# Proyek6_Joy.net
KiCad netlist of a schematic drawn in EasyEDA
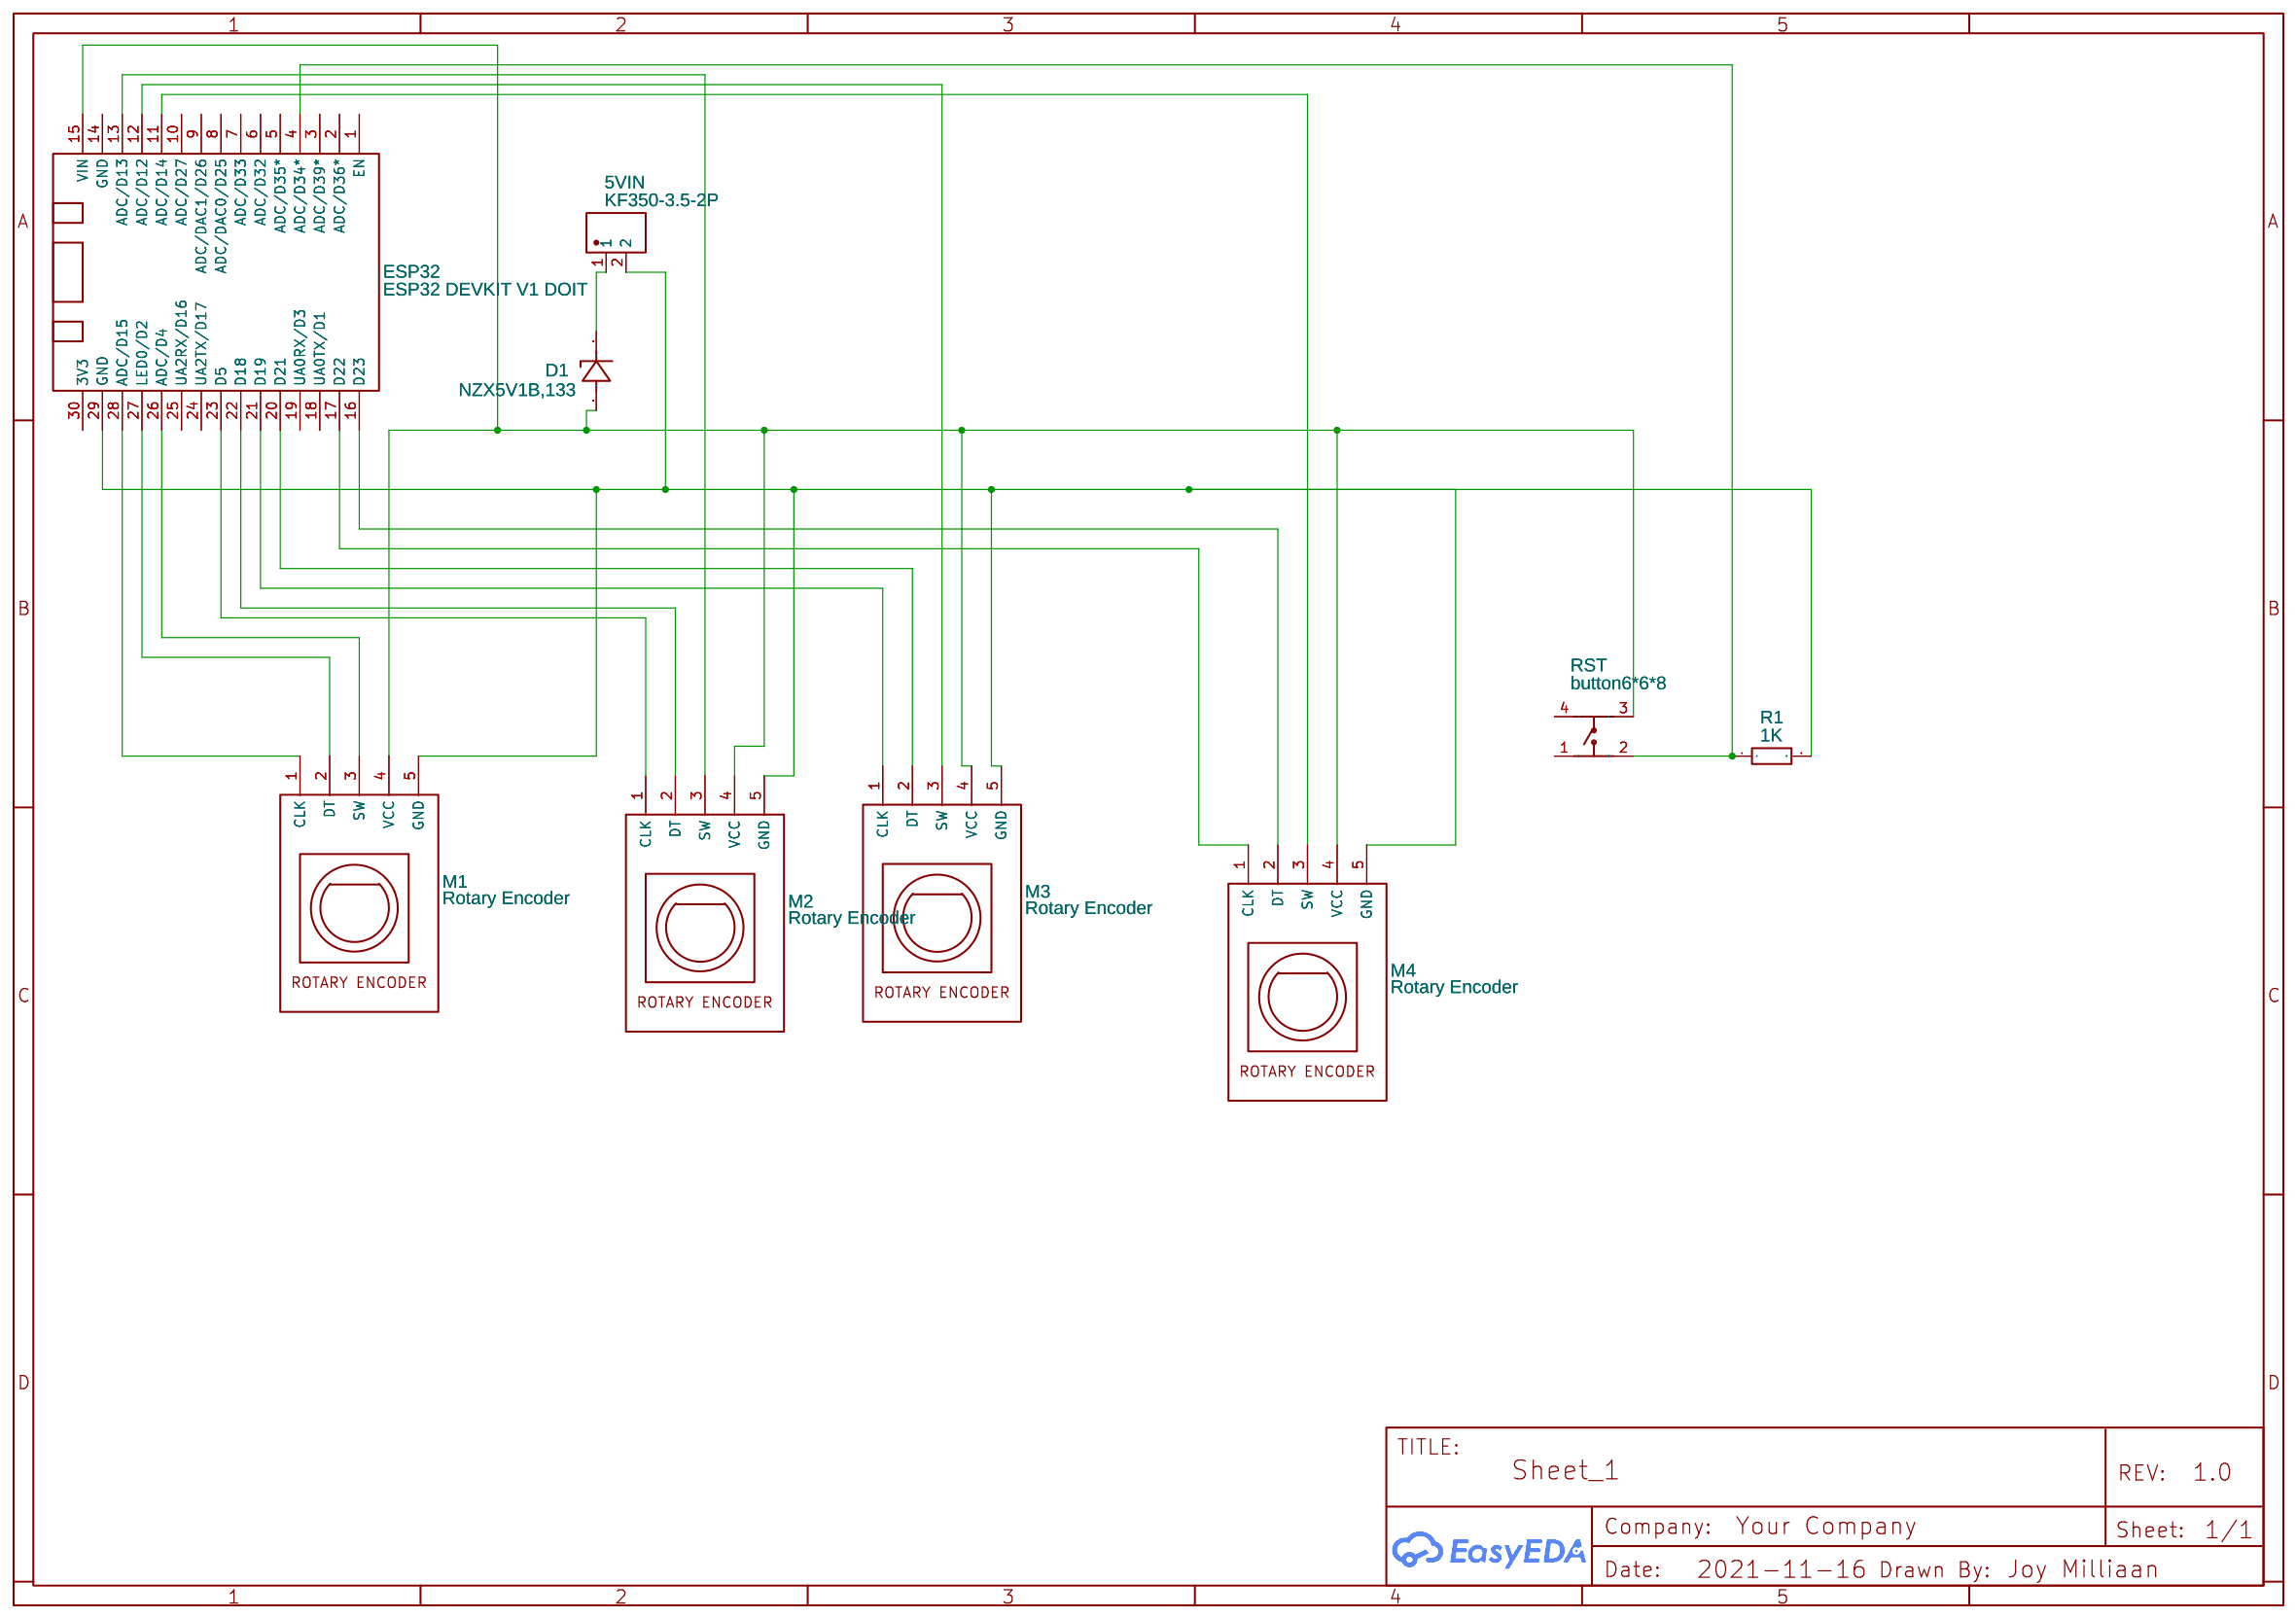
[diagram p0: schematic sheet]

(export (version "E")
  (design (tool "Eeschema 10.0.6"))
  (components
    (comp (ref "5VIN")
      (value "KF350-3.5-2P")
      (fields (field (name "BOM_Supplier Part") "C474892"))
      (libsource (lib "") (part "KF350-3.5-2P"))
    )
    (comp (ref "D1")
      (value "NZX5V1B,133")
      (fields (field (name "BOM_Supplier Part") "C551729"))
      (libsource (lib "") (part "NZX5V1B,133"))
    )
    (comp (ref "ESP32") (value "ESP32 DEVKIT V1 DOIT") (libsource (lib "") (part "ESP32 DEVKIT V1 DOIT")))
    (comp (ref "M1")
      (value "Rotary Encoder")
      (fields (field (name "BOM_Manufacturer Part") "KY-040"))
      (libsource (lib "") (part "Rotary Encoder"))
    )
    (comp (ref "M2")
      (value "Rotary Encoder")
      (fields (field (name "BOM_Manufacturer Part") "KY-040"))
      (libsource (lib "") (part "Rotary Encoder"))
    )
    (comp (ref "M3")
      (value "Rotary Encoder")
      (fields (field (name "BOM_Manufacturer Part") "KY-040"))
      (libsource (lib "") (part "Rotary Encoder"))
    )
    (comp (ref "M4")
      (value "Rotary Encoder")
      (fields (field (name "BOM_Manufacturer Part") "KY-040"))
      (libsource (lib "") (part "Rotary Encoder"))
    )
    (comp (ref "R1")
      (value "1K")
      (fields
        (field (name "BOM_Manufacturer Part") "CFR0W4J0102A50")
        (field (name "BOM_Supplier Part") "C61293")
      )
      (libsource (lib "") (part "CFR0W4J0102A50"))
    )
    (comp (ref "RST")
      (value "button6*6*8")
      (fields (field (name "BOM_Supplier Part") "C59982"))
      (libsource (lib "") (part "button6*6*8"))
    )
  )
  (nets
    (net (code "1") (name "Net-(D1-A)") (class "Default")
      (node (ref "D1") (pin "2") (pinfunction "A_2") (pintype "unspecified"))
      (node (ref "ESP32") (pin "15") (pinfunction "VIN_15") (pintype "input"))
      (node (ref "M1") (pin "4") (pinfunction "VCC_4") (pintype "unspecified"))
      (node (ref "M2") (pin "4") (pinfunction "VCC_4") (pintype "unspecified"))
      (node (ref "M3") (pin "4") (pinfunction "VCC_4") (pintype "unspecified"))
      (node (ref "M4") (pin "4") (pinfunction "VCC_4") (pintype "unspecified"))
      (node (ref "RST") (pin "3") (pinfunction "3_3") (pintype "unspecified"))
    )
    (net (code "2") (name "Net-(D1-C)") (class "Default")
      (node (ref "5VIN") (pin "1") (pinfunction "1_1") (pintype "unspecified"))
      (node (ref "D1") (pin "1") (pinfunction "C_1") (pintype "unspecified"))
    )
    (net (code "3") (name "Net-(ESP32-ADC{slash}D4)") (class "Default")
      (node (ref "ESP32") (pin "26") (pinfunction "ADC/D4_26") (pintype "bidirectional"))
      (node (ref "M1") (pin "3") (pinfunction "SW_3") (pintype "unspecified"))
    )
    (net (code "4") (name "Net-(ESP32-ADC{slash}D12)") (class "Default")
      (node (ref "ESP32") (pin "12") (pinfunction "ADC/D12_12") (pintype "bidirectional"))
      (node (ref "M3") (pin "3") (pinfunction "SW_3") (pintype "unspecified"))
    )
    (net (code "5") (name "Net-(ESP32-ADC{slash}D13)") (class "Default")
      (node (ref "ESP32") (pin "13") (pinfunction "ADC/D13_13") (pintype "bidirectional"))
      (node (ref "M2") (pin "3") (pinfunction "SW_3") (pintype "unspecified"))
    )
    (net (code "6") (name "Net-(ESP32-ADC{slash}D14)") (class "Default")
      (node (ref "ESP32") (pin "11") (pinfunction "ADC/D14_11") (pintype "bidirectional"))
      (node (ref "M4") (pin "3") (pinfunction "SW_3") (pintype "unspecified"))
    )
    (net (code "7") (name "Net-(ESP32-ADC{slash}D15)") (class "Default")
      (node (ref "ESP32") (pin "28") (pinfunction "ADC/D15_28") (pintype "bidirectional"))
      (node (ref "M1") (pin "1") (pinfunction "CLK_1") (pintype "unspecified"))
    )
    (net (code "8") (name "Net-(ESP32-ADC{slash}D34*)") (class "Default")
      (node (ref "ESP32") (pin "4") (pinfunction "ADC/D34*_4") (pintype "input"))
      (node (ref "R1") (pin "1") (pinfunction "1_1") (pintype "input"))
      (node (ref "RST") (pin "2") (pinfunction "2_2") (pintype "unspecified"))
    )
    (net (code "9") (name "Net-(ESP32-D5)") (class "Default")
      (node (ref "ESP32") (pin "23") (pinfunction "D5_23") (pintype "bidirectional"))
      (node (ref "M2") (pin "1") (pinfunction "CLK_1") (pintype "unspecified"))
    )
    (net (code "10") (name "Net-(ESP32-D18)") (class "Default")
      (node (ref "ESP32") (pin "22") (pinfunction "D18_22") (pintype "bidirectional"))
      (node (ref "M2") (pin "2") (pinfunction "DT_2") (pintype "unspecified"))
    )
    (net (code "11") (name "Net-(ESP32-D19)") (class "Default")
      (node (ref "ESP32") (pin "21") (pinfunction "D19_21") (pintype "bidirectional"))
      (node (ref "M3") (pin "1") (pinfunction "CLK_1") (pintype "unspecified"))
    )
    (net (code "12") (name "Net-(ESP32-D21)") (class "Default")
      (node (ref "ESP32") (pin "20") (pinfunction "D21_20") (pintype "bidirectional"))
      (node (ref "M3") (pin "2") (pinfunction "DT_2") (pintype "unspecified"))
    )
    (net (code "13") (name "Net-(ESP32-D22)") (class "Default")
      (node (ref "ESP32") (pin "17") (pinfunction "D22_17") (pintype "bidirectional"))
      (node (ref "M4") (pin "1") (pinfunction "CLK_1") (pintype "unspecified"))
    )
    (net (code "14") (name "Net-(ESP32-D23)") (class "Default")
      (node (ref "ESP32") (pin "16") (pinfunction "D23_16") (pintype "bidirectional"))
      (node (ref "M4") (pin "2") (pinfunction "DT_2") (pintype "unspecified"))
    )
    (net (code "15") (name "Net-(ESP32-LED0{slash}D2)") (class "Default")
      (node (ref "ESP32") (pin "27") (pinfunction "LED0/D2_27") (pintype "bidirectional"))
      (node (ref "M1") (pin "2") (pinfunction "DT_2") (pintype "unspecified"))
    )
    (net (code "16") (name "Net-(M1-GND)") (class "Default")
      (node (ref "5VIN") (pin "2") (pinfunction "2_2") (pintype "unspecified"))
      (node (ref "ESP32") (pin "29") (pinfunction "GND_29") (pintype "bidirectional"))
      (node (ref "M1") (pin "5") (pinfunction "GND_5") (pintype "unspecified"))
      (node (ref "M2") (pin "5") (pinfunction "GND_5") (pintype "unspecified"))
      (node (ref "M3") (pin "5") (pinfunction "GND_5") (pintype "unspecified"))
      (node (ref "M4") (pin "5") (pinfunction "GND_5") (pintype "unspecified"))
      (node (ref "R1") (pin "2") (pinfunction "2_2") (pintype "input"))
    )
    (net (code "17") (name "unconnected-(ESP32-3V3-Pad30)") (class "Default")
      (node (ref "ESP32") (pin "30") (pinfunction "3V3_30") (pintype "bidirectional"))
    )
    (net (code "18") (name "unconnected-(ESP32-ADC{slash}D27-Pad10)") (class "Default")
      (node (ref "ESP32") (pin "10") (pinfunction "ADC/D27_10") (pintype "bidirectional"))
    )
    (net (code "19") (name "unconnected-(ESP32-ADC{slash}D32-Pad6)") (class "Default")
      (node (ref "ESP32") (pin "6") (pinfunction "ADC/D32_6") (pintype "bidirectional"))
    )
    (net (code "20") (name "unconnected-(ESP32-ADC{slash}D33-Pad7)") (class "Default")
      (node (ref "ESP32") (pin "7") (pinfunction "ADC/D33_7") (pintype "bidirectional"))
    )
    (net (code "21") (name "unconnected-(ESP32-ADC{slash}D35*-Pad5)") (class "Default")
      (node (ref "ESP32") (pin "5") (pinfunction "ADC/D35*_5") (pintype "input"))
    )
    (net (code "22") (name "unconnected-(ESP32-ADC{slash}D36*-Pad2)") (class "Default")
      (node (ref "ESP32") (pin "2") (pinfunction "ADC/D36*_2") (pintype "input"))
    )
    (net (code "23") (name "unconnected-(ESP32-ADC{slash}D39*-Pad3)") (class "Default")
      (node (ref "ESP32") (pin "3") (pinfunction "ADC/D39*_3") (pintype "input"))
    )
    (net (code "24") (name "unconnected-(ESP32-ADC{slash}DAC0{slash}D25-Pad8)") (class "Default")
      (node (ref "ESP32") (pin "8") (pinfunction "ADC/DAC0/D25_8") (pintype "bidirectional"))
    )
    (net (code "25") (name "unconnected-(ESP32-ADC{slash}DAC1{slash}D26-Pad9)") (class "Default")
      (node (ref "ESP32") (pin "9") (pinfunction "ADC/DAC1/D26_9") (pintype "bidirectional"))
    )
    (net (code "26") (name "unconnected-(ESP32-EN-Pad1)") (class "Default")
      (node (ref "ESP32") (pin "1") (pinfunction "EN_1") (pintype "bidirectional"))
    )
    (net (code "27") (name "unconnected-(ESP32-GND-Pad14)") (class "Default")
      (node (ref "ESP32") (pin "14") (pinfunction "GND_14") (pintype "bidirectional"))
    )
    (net (code "28") (name "unconnected-(ESP32-UA0RX{slash}D3-Pad19)") (class "Default")
      (node (ref "ESP32") (pin "19") (pinfunction "UA0RX/D3_19") (pintype "bidirectional"))
    )
    (net (code "29") (name "unconnected-(ESP32-UA0TX{slash}D1-Pad18)") (class "Default")
      (node (ref "ESP32") (pin "18") (pinfunction "UA0TX/D1_18") (pintype "bidirectional"))
    )
    (net (code "30") (name "unconnected-(ESP32-UA2RX{slash}D16-Pad25)") (class "Default")
      (node (ref "ESP32") (pin "25") (pinfunction "UA2RX/D16_25") (pintype "bidirectional"))
    )
    (net (code "31") (name "unconnected-(ESP32-UA2TX{slash}D17-Pad24)") (class "Default")
      (node (ref "ESP32") (pin "24") (pinfunction "UA2TX/D17_24") (pintype "bidirectional"))
    )
    (net (code "32") (name "unconnected-(RST-Pad1)") (class "Default")
      (node (ref "RST") (pin "1") (pinfunction "1_1") (pintype "unspecified"))
    )
    (net (code "33") (name "unconnected-(RST-Pad4)") (class "Default")
      (node (ref "RST") (pin "4") (pinfunction "4_4") (pintype "unspecified"))
    )
  )
)
